# Port.net
KiCad netlist of a schematic drawn in Altium Designer
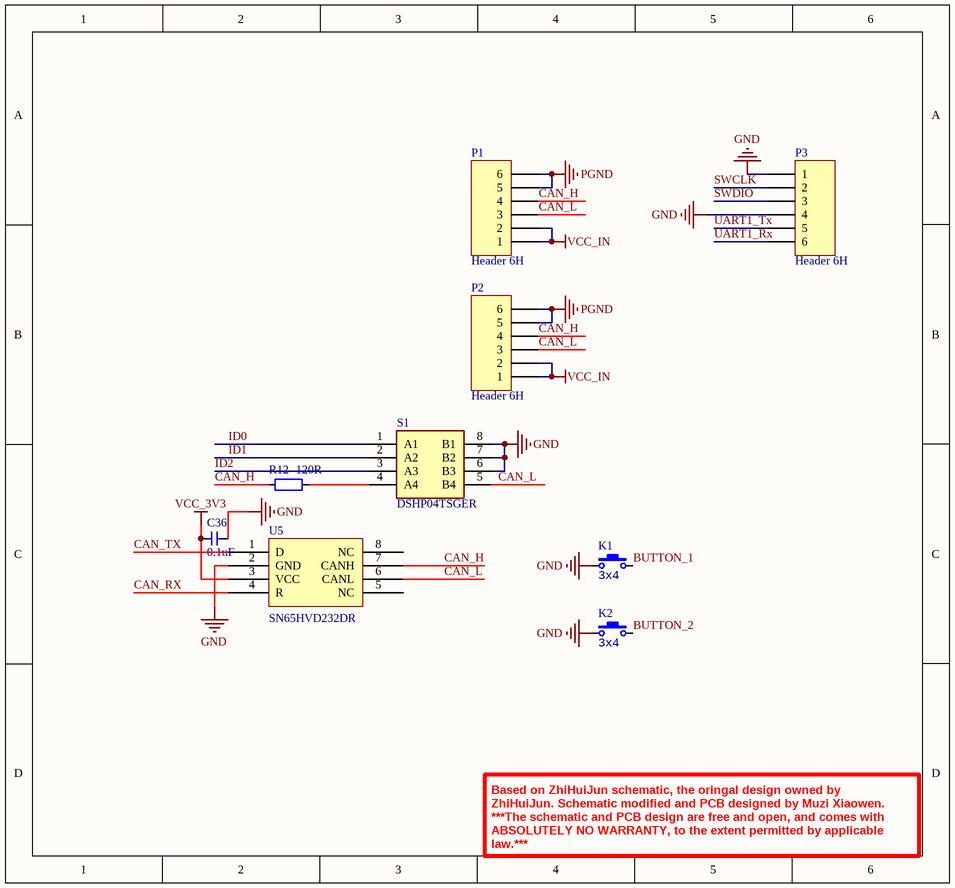
[diagram p0: Port.SchDoc]

(export (version "E")
  (design (tool "Eeschema 10.0.6"))
  (components
    (comp (ref "C36")
      (value "0.1uF")
      (footprint "motor42-lib:CAP_0402")
      (description "Capacitor")
      (libsource (lib "MyPcbLib") (part "电容-0402"))
    )
    (comp (ref "K1")
      (value "3x4")
      (footprint "ButtonTACT_3x4x2_180")
      (description "Button")
      (fields (field (name "Comment") "TACT 2P"))
      (libsource (lib "KitSprout") (part "ButtonTACT_3x4x2_180"))
    )
    (comp (ref "K2")
      (value "3x4")
      (footprint "ButtonTACT_3x4x2_180")
      (description "Button")
      (fields (field (name "Comment") "TACT 2P"))
      (libsource (lib "KitSprout") (part "ButtonTACT_3x4x2_180"))
    )
    (comp (ref "P1")
      (value "Header 6H")
      (footprint "CONN-TH_HC-ZH1.5-6A-s")
      (description "Header, 6-Pin, Right Angle")
      (fields (field (name "PUBLISHER") "Altium Limited"))
      (libsource (lib "Miscellaneous Connectors") (part "Header 6H"))
    )
    (comp (ref "P2")
      (value "Header 6H")
      (footprint "CONN-TH_HC-ZH1.5-6A-s")
      (description "Header, 6-Pin, Right Angle")
      (fields (field (name "PUBLISHER") "Altium Limited"))
      (libsource (lib "Miscellaneous Connectors") (part "Header 6H"))
    )
    (comp (ref "P3")
      (value "Header 6H")
      (footprint "CONN-TH_HC-ZH1.5-6A-s")
      (description "Header, 6-Pin, Right Angle")
      (fields (field (name "PUBLISHER") "Altium Limited"))
      (libsource (lib "") (part "Header 6H_1"))
    )
    (comp (ref "R12")
      (value "120R")
      (footprint "RES_0402")
      (description "Resistor")
      (libsource (lib "MyPcbLib") (part "电阻-0402"))
    )
    (comp (ref "S1")
      (value "DSHP04TSGER")
      (footprint "SW-SMD_DSHP04TS-S")
      (description "DIP Switches / SIP Switches 4 pos. low profile Btm Seal Tape J Bend")
      (fields
        (field (name "MOUSER PART NUMBER") "774-218-4LPSTJ")
        (field (name "MANUFACTURER_PART_NUMBER") "218-4LPSTJ")
      )
      (libsource (lib "Schlib1") (part "218-4LPSTJ"))
    )
    (comp (ref "U5")
      (value "SN65HVD232D")
      (footprint "so-8")
      (fields
        (field (name "MANUFACTURER") "Texas Instruments")
        (field (name "MANUFACTURER PART NUMBER") "SN65HVD232DR")
      )
      (libsource (lib "MyPcbLib") (part "SN65HVD232D"))
    )
  )
  (nets
    (net (code "1") (name "/BUTTON_1") (class "Default")
      (node (ref "K1") (pin "2") (pinfunction "2_2") (pintype "passive"))
    )
    (net (code "2") (name "/BUTTON_2") (class "Default")
      (node (ref "K2") (pin "2") (pinfunction "2_2") (pintype "passive"))
    )
    (net (code "3") (name "/CAN_H") (class "Default")
      (node (ref "P1") (pin "4") (pinfunction "4_4") (pintype "passive"))
      (node (ref "P2") (pin "4") (pinfunction "4_4") (pintype "passive"))
      (node (ref "R12") (pin "1") (pinfunction "1_1") (pintype "passive"))
      (node (ref "U5") (pin "7") (pinfunction "CANH_7") (pintype "passive"))
    )
    (net (code "4") (name "/CAN_L") (class "Default")
      (node (ref "P1") (pin "3") (pinfunction "3_3") (pintype "passive"))
      (node (ref "P2") (pin "3") (pinfunction "3_3") (pintype "passive"))
      (node (ref "S1") (pin "5") (pinfunction "B4_5") (pintype "passive"))
      (node (ref "U5") (pin "6") (pinfunction "CANL_6") (pintype "passive"))
    )
    (net (code "5") (name "/CAN_RX") (class "Default")
      (node (ref "U5") (pin "4") (pinfunction "R_4") (pintype "passive"))
    )
    (net (code "6") (name "/CAN_TX") (class "Default")
      (node (ref "U5") (pin "1") (pinfunction "D_1") (pintype "passive"))
    )
    (net (code "7") (name "/ID0") (class "Default")
      (node (ref "S1") (pin "1") (pinfunction "A1_1") (pintype "passive"))
    )
    (net (code "8") (name "/ID1") (class "Default")
      (node (ref "S1") (pin "2") (pinfunction "A2_2") (pintype "passive"))
    )
    (net (code "9") (name "/ID2") (class "Default")
      (node (ref "S1") (pin "3") (pinfunction "A3_3") (pintype "passive"))
    )
    (net (code "10") (name "/SWCLK") (class "Default")
      (node (ref "P3") (pin "2") (pinfunction "2_2") (pintype "passive"))
    )
    (net (code "11") (name "/SWDIO") (class "Default")
      (node (ref "P3") (pin "3") (pinfunction "3_3") (pintype "passive"))
    )
    (net (code "12") (name "/UART1_Rx") (class "Default")
      (node (ref "P3") (pin "6") (pinfunction "6_6") (pintype "passive"))
    )
    (net (code "13") (name "/UART1_Tx") (class "Default")
      (node (ref "P3") (pin "5") (pinfunction "5_5") (pintype "passive"))
    )
    (net (code "14") (name "GND") (class "Default")
      (node (ref "C36") (pin "1") (pinfunction "1_1") (pintype "passive"))
      (node (ref "K1") (pin "1") (pinfunction "1_1") (pintype "passive"))
      (node (ref "K2") (pin "1") (pinfunction "1_1") (pintype "passive"))
      (node (ref "P3") (pin "1") (pinfunction "1_1") (pintype "passive"))
      (node (ref "P3") (pin "4") (pinfunction "4_4") (pintype "passive"))
      (node (ref "S1") (pin "6") (pinfunction "B3_6") (pintype "passive"))
      (node (ref "S1") (pin "7") (pinfunction "B2_7") (pintype "passive"))
      (node (ref "S1") (pin "8") (pinfunction "B1_8") (pintype "passive"))
      (node (ref "U5") (pin "2") (pinfunction "GND_2") (pintype "passive"))
    )
    (net (code "15") (name "Net-(S1-A4)") (class "Default")
      (node (ref "R12") (pin "2") (pinfunction "2_2") (pintype "passive"))
      (node (ref "S1") (pin "4") (pinfunction "A4_4") (pintype "passive"))
    )
    (net (code "16") (name "PGND") (class "Default")
      (node (ref "P1") (pin "5") (pinfunction "5_5") (pintype "passive"))
      (node (ref "P1") (pin "6") (pinfunction "6_6") (pintype "passive"))
      (node (ref "P2") (pin "5") (pinfunction "5_5") (pintype "passive"))
      (node (ref "P2") (pin "6") (pinfunction "6_6") (pintype "passive"))
    )
    (net (code "17") (name "VCC_3V3") (class "Default")
      (node (ref "C36") (pin "2") (pinfunction "2_2") (pintype "passive"))
      (node (ref "U5") (pin "3") (pinfunction "VCC_3") (pintype "passive"))
    )
    (net (code "18") (name "VCC_IN") (class "Default")
      (node (ref "P1") (pin "1") (pinfunction "1_1") (pintype "passive"))
      (node (ref "P1") (pin "2") (pinfunction "2_2") (pintype "passive"))
      (node (ref "P2") (pin "1") (pinfunction "1_1") (pintype "passive"))
      (node (ref "P2") (pin "2") (pinfunction "2_2") (pintype "passive"))
    )
    (net (code "19") (name "unconnected-(U5-NC-Pad5)") (class "Default")
      (node (ref "U5") (pin "5") (pinfunction "NC_5") (pintype "passive"))
    )
    (net (code "20") (name "unconnected-(U5-NC-Pad8)") (class "Default")
      (node (ref "U5") (pin "8") (pinfunction "NC_8") (pintype "passive"))
    )
  )
)
